# akabeacon_circle_MDBT40_type1.net
KiCad netlist of a schematic drawn in EAGLE
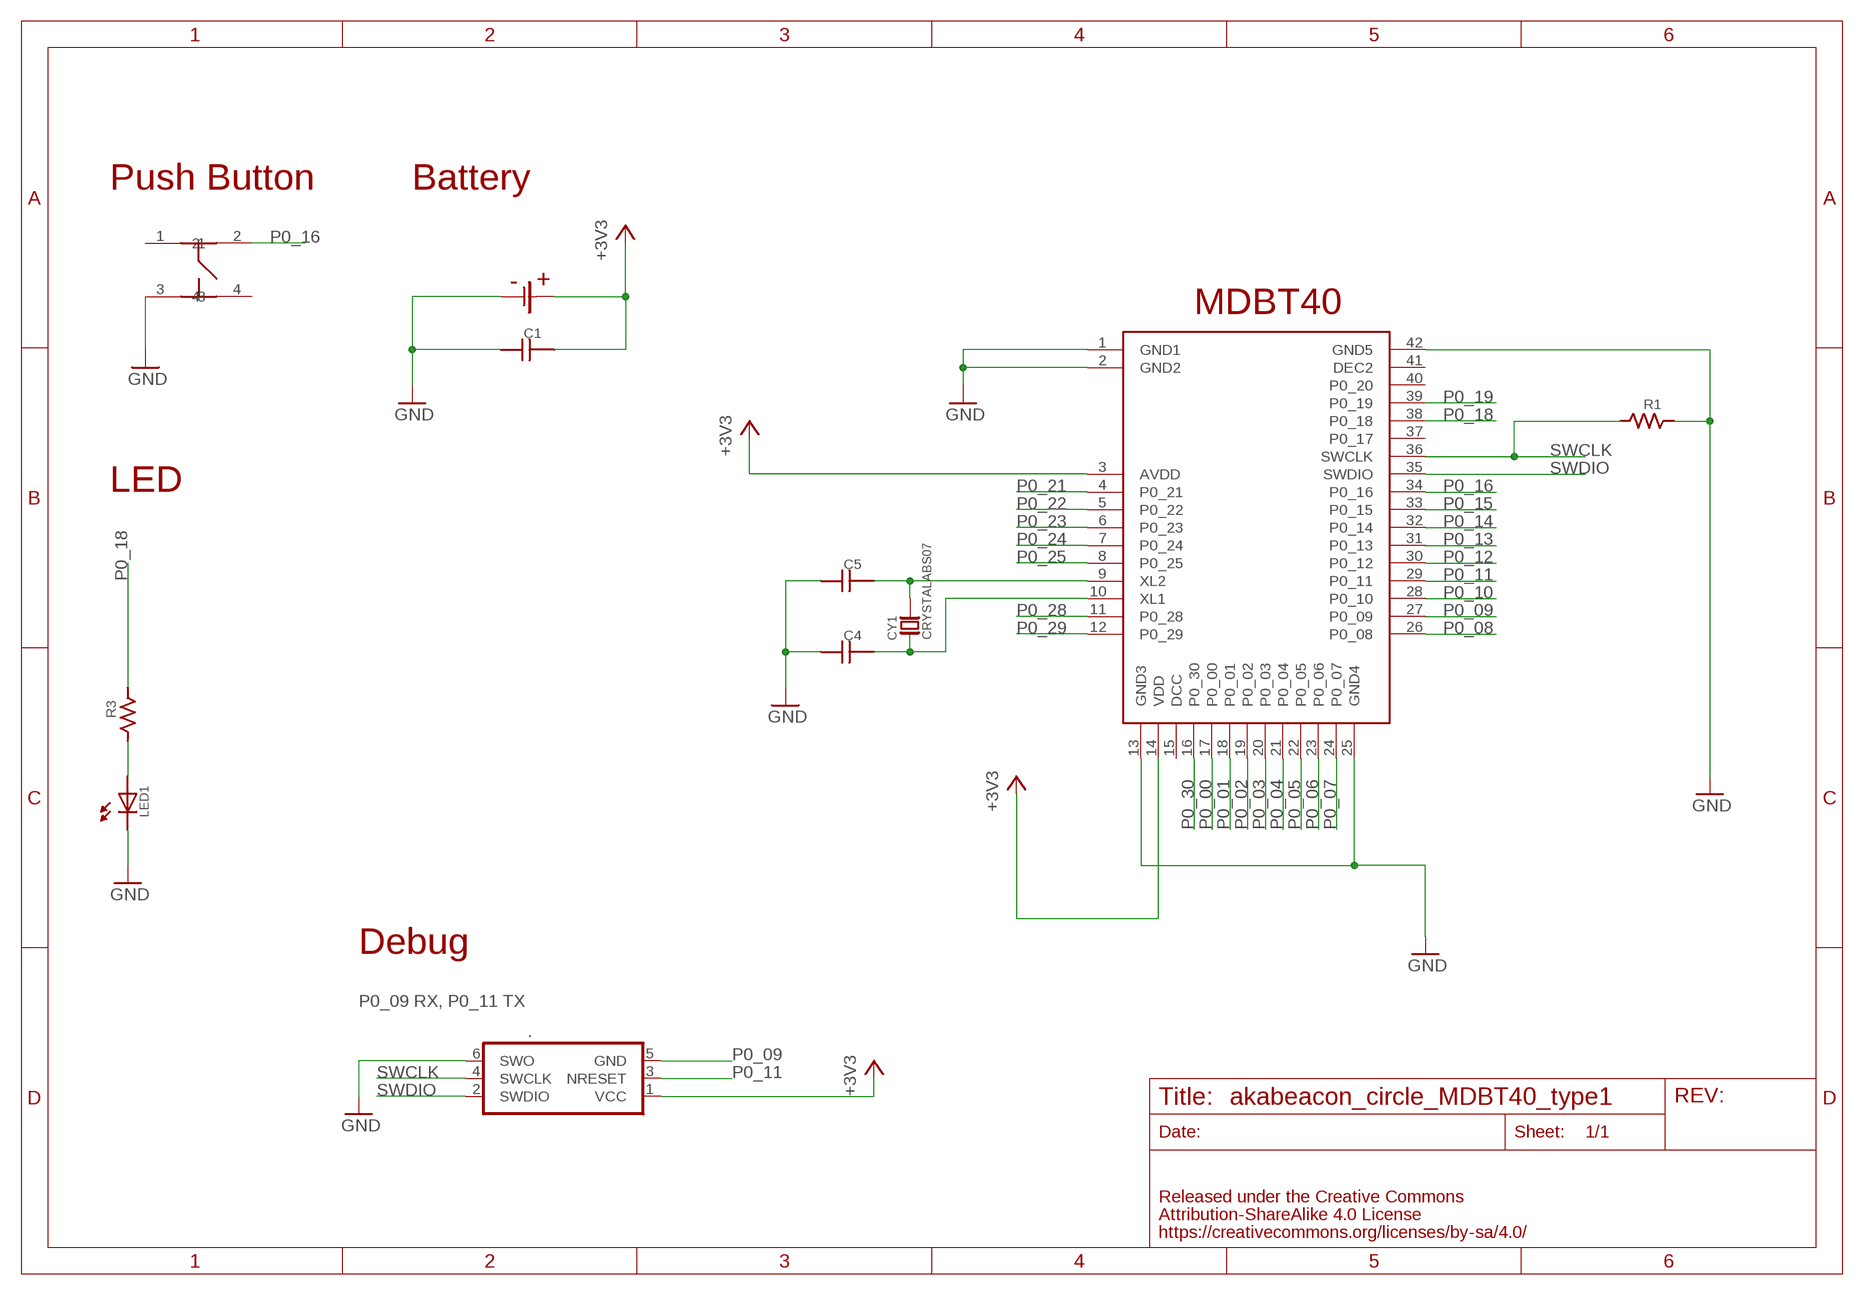
[diagram p0: schematic, sheet 1]

(export (version "E")
  (design (tool "Eeschema 10.0.6"))
  (components
    (comp (ref ".")
      (value "TC2030-IDC-NL")
      (footprint "eagle-import:TC2030-IDC-NL")
      (libsource (lib "eagle-import") (part "TC2030-IDC-NL"))
    )
    (comp (ref "C1")
      (value "CAPACITOR-0603")
      (footprint "eagle-import:0603")
      (libsource (lib "eagle-import") (part "CAPACITOR-0603"))
    )
    (comp (ref "C4")
      (value "CAPACITOR-0603")
      (footprint "eagle-import:0603")
      (libsource (lib "eagle-import") (part "CAPACITOR-0603"))
    )
    (comp (ref "C5")
      (value "CAPACITOR-0603")
      (footprint "eagle-import:0603")
      (libsource (lib "eagle-import") (part "CAPACITOR-0603"))
    )
    (comp (ref "CY1")
      (value "CRYSTALABS07")
      (footprint "eagle-import:ABRACOM-ABS07-32.768KHZ")
      (libsource (lib "eagle-import") (part "CRYSTALABS07"))
    )
    (comp (ref "LED1")
      (value "LED-0603")
      (footprint "eagle-import:0603")
      (libsource (lib "eagle-import") (part "LED-0603"))
    )
    (comp (ref "R1")
      (value "RESISTOR-0603")
      (footprint "eagle-import:0603")
      (libsource (lib "eagle-import") (part "RESISTOR-0603"))
    )
    (comp (ref "R3")
      (value "RESISTOR-0603")
      (footprint "eagle-import:0603")
      (libsource (lib "eagle-import") (part "RESISTOR-0603"))
    )
    (comp (ref "U$1")
      (value "RAYTAC-MDBT40")
      (footprint "eagle-import:RAYTAC-MDBT40")
      (libsource (lib "eagle-import") (part "RAYTAC-MDBT40"))
    )
    (comp (ref "U$2")
      (value "CH031-2477LF")
      (footprint "eagle-import:CH031-2477LF")
      (libsource (lib "eagle-import") (part "CH031-2477LF"))
    )
    (comp (ref "U$5")
      (value "SWICTH-4P(KMR2)")
      (footprint "eagle-import:SWITCH-4P(KMR2)")
      (libsource (lib "eagle-import") (part "SWICTH-4P(KMR2)"))
    )
  )
  (nets
    (net (code "1") (name "+3V3") (class "Default")
      (node (ref ".") (pin "1") (pinfunction "VCC_1") (pintype "passive"))
      (node (ref "C1") (pin "2") (pinfunction "2_2") (pintype "passive"))
      (node (ref "U$1") (pin "14") (pinfunction "VDD_14") (pintype "bidirectional"))
      (node (ref "U$1") (pin "3") (pinfunction "AVDD_3") (pintype "bidirectional"))
      (node (ref "U$2") (pin "+") (pinfunction "+_+") (pintype "bidirectional"))
    )
    (net (code "2") (name "/P0_00") (class "Default")
      (node (ref "U$1") (pin "17") (pinfunction "P0_00_17") (pintype "bidirectional"))
    )
    (net (code "3") (name "/P0_01") (class "Default")
      (node (ref "U$1") (pin "18") (pinfunction "P0_01_18") (pintype "bidirectional"))
    )
    (net (code "4") (name "/P0_02") (class "Default")
      (node (ref "U$1") (pin "19") (pinfunction "P0_02_19") (pintype "bidirectional"))
    )
    (net (code "5") (name "/P0_03") (class "Default")
      (node (ref "U$1") (pin "20") (pinfunction "P0_03_20") (pintype "bidirectional"))
    )
    (net (code "6") (name "/P0_04") (class "Default")
      (node (ref "U$1") (pin "21") (pinfunction "P0_04_21") (pintype "bidirectional"))
    )
    (net (code "7") (name "/P0_05") (class "Default")
      (node (ref "U$1") (pin "22") (pinfunction "P0_05_22") (pintype "bidirectional"))
    )
    (net (code "8") (name "/P0_06") (class "Default")
      (node (ref "U$1") (pin "23") (pinfunction "P0_06_23") (pintype "bidirectional"))
    )
    (net (code "9") (name "/P0_07") (class "Default")
      (node (ref "U$1") (pin "24") (pinfunction "P0_07_24") (pintype "bidirectional"))
    )
    (net (code "10") (name "/P0_08") (class "Default")
      (node (ref "U$1") (pin "26") (pinfunction "P0_08_26") (pintype "bidirectional"))
    )
    (net (code "11") (name "/P0_09") (class "Default")
      (node (ref ".") (pin "5") (pinfunction "GND_5") (pintype "passive"))
      (node (ref "U$1") (pin "27") (pinfunction "P0_09_27") (pintype "bidirectional"))
    )
    (net (code "12") (name "/P0_10") (class "Default")
      (node (ref "U$1") (pin "28") (pinfunction "P0_10_28") (pintype "bidirectional"))
    )
    (net (code "13") (name "/P0_11") (class "Default")
      (node (ref ".") (pin "3") (pinfunction "NRESET_3") (pintype "passive"))
      (node (ref "U$1") (pin "29") (pinfunction "P0_11_29") (pintype "bidirectional"))
    )
    (net (code "14") (name "/P0_12") (class "Default")
      (node (ref "U$1") (pin "30") (pinfunction "P0_12_30") (pintype "bidirectional"))
    )
    (net (code "15") (name "/P0_13") (class "Default")
      (node (ref "U$1") (pin "31") (pinfunction "P0_13_31") (pintype "bidirectional"))
    )
    (net (code "16") (name "/P0_14") (class "Default")
      (node (ref "U$1") (pin "32") (pinfunction "P0_14_32") (pintype "bidirectional"))
    )
    (net (code "17") (name "/P0_15") (class "Default")
      (node (ref "U$1") (pin "33") (pinfunction "P0_15_33") (pintype "bidirectional"))
    )
    (net (code "18") (name "/P0_16") (class "Default")
      (node (ref "U$1") (pin "34") (pinfunction "P0_16_34") (pintype "bidirectional"))
      (node (ref "U$5") (pin "2") (pinfunction "2_2") (pintype "bidirectional"))
    )
    (net (code "19") (name "/P0_18") (class "Default")
      (node (ref "R3") (pin "2") (pinfunction "2_2") (pintype "bidirectional"))
      (node (ref "U$1") (pin "38") (pinfunction "P0_18_38") (pintype "bidirectional"))
    )
    (net (code "20") (name "/P0_19") (class "Default")
      (node (ref "U$1") (pin "39") (pinfunction "P0_19_39") (pintype "bidirectional"))
    )
    (net (code "21") (name "/P0_21") (class "Default")
      (node (ref "U$1") (pin "4") (pinfunction "P0_21_4") (pintype "bidirectional"))
    )
    (net (code "22") (name "/P0_22") (class "Default")
      (node (ref "U$1") (pin "5") (pinfunction "P0_22_5") (pintype "bidirectional"))
    )
    (net (code "23") (name "/P0_23") (class "Default")
      (node (ref "U$1") (pin "6") (pinfunction "P0_23_6") (pintype "bidirectional"))
    )
    (net (code "24") (name "/P0_24") (class "Default")
      (node (ref "U$1") (pin "7") (pinfunction "P0_24_7") (pintype "bidirectional"))
    )
    (net (code "25") (name "/P0_25") (class "Default")
      (node (ref "U$1") (pin "8") (pinfunction "P0_25_8") (pintype "bidirectional"))
    )
    (net (code "26") (name "/P0_28") (class "Default")
      (node (ref "U$1") (pin "11") (pinfunction "P0_28_11") (pintype "bidirectional"))
    )
    (net (code "27") (name "/P0_29") (class "Default")
      (node (ref "U$1") (pin "12") (pinfunction "P0_29_12") (pintype "bidirectional"))
    )
    (net (code "28") (name "/P0_30") (class "Default")
      (node (ref "U$1") (pin "16") (pinfunction "P0_30_16") (pintype "bidirectional"))
    )
    (net (code "29") (name "/SWCLK") (class "Default")
      (node (ref ".") (pin "4") (pinfunction "SWCLK_4") (pintype "passive"))
      (node (ref "R1") (pin "1") (pinfunction "1_1") (pintype "bidirectional"))
      (node (ref "U$1") (pin "36") (pinfunction "SWCLK_36") (pintype "bidirectional"))
    )
    (net (code "30") (name "/SWDIO") (class "Default")
      (node (ref ".") (pin "2") (pinfunction "SWDIO_2") (pintype "passive"))
      (node (ref "U$1") (pin "35") (pinfunction "SWDIO_35") (pintype "bidirectional"))
    )
    (net (code "31") (name "GND") (class "Default")
      (node (ref ".") (pin "6") (pinfunction "SWO_6") (pintype "passive"))
      (node (ref "C1") (pin "1") (pinfunction "1_1") (pintype "passive"))
      (node (ref "C4") (pin "1") (pinfunction "1_1") (pintype "passive"))
      (node (ref "C5") (pin "1") (pinfunction "1_1") (pintype "passive"))
      (node (ref "LED1") (pin "CATHODE") (pinfunction "CATHODE_CATHODE") (pintype "passive"))
      (node (ref "R1") (pin "2") (pinfunction "2_2") (pintype "bidirectional"))
      (node (ref "U$1") (pin "1") (pinfunction "GND1_1") (pintype "bidirectional"))
      (node (ref "U$1") (pin "13") (pinfunction "GND3_13") (pintype "bidirectional"))
      (node (ref "U$1") (pin "2") (pinfunction "GND2_2") (pintype "bidirectional"))
      (node (ref "U$1") (pin "25") (pinfunction "GND4_25") (pintype "bidirectional"))
      (node (ref "U$1") (pin "42") (pinfunction "GND5_42") (pintype "bidirectional"))
      (node (ref "U$2") (pin "-") (pinfunction "-_-") (pintype "bidirectional"))
      (node (ref "U$5") (pin "3") (pinfunction "3_3") (pintype "bidirectional"))
    )
    (net (code "32") (name "Net-(LED1-PadANODE)") (class "Default")
      (node (ref "LED1") (pin "ANODE") (pinfunction "ANODE_ANODE") (pintype "passive"))
      (node (ref "R3") (pin "1") (pinfunction "1_1") (pintype "bidirectional"))
    )
    (net (code "33") (name "Net-(U$1-XL1)") (class "Default")
      (node (ref "C4") (pin "2") (pinfunction "2_2") (pintype "passive"))
      (node (ref "CY1") (pin "P$1") (pinfunction "P$1_P$1") (pintype "bidirectional"))
      (node (ref "U$1") (pin "10") (pinfunction "XL1_10") (pintype "bidirectional"))
    )
    (net (code "34") (name "Net-(U$1-XL2)") (class "Default")
      (node (ref "C5") (pin "2") (pinfunction "2_2") (pintype "passive"))
      (node (ref "CY1") (pin "P$2") (pinfunction "P$2_P$2") (pintype "bidirectional"))
      (node (ref "U$1") (pin "9") (pinfunction "XL2_9") (pintype "bidirectional"))
    )
    (net (code "35") (name "unconnected-(U$1-DCC-Pad15)") (class "Default")
      (node (ref "U$1") (pin "15") (pinfunction "DCC_15") (pintype "bidirectional"))
    )
    (net (code "36") (name "unconnected-(U$1-DEC2-Pad41)") (class "Default")
      (node (ref "U$1") (pin "41") (pinfunction "DEC2_41") (pintype "bidirectional"))
    )
    (net (code "37") (name "unconnected-(U$1-P0_17-Pad37)") (class "Default")
      (node (ref "U$1") (pin "37") (pinfunction "P0_17_37") (pintype "bidirectional"))
    )
    (net (code "38") (name "unconnected-(U$1-P0_20-Pad40)") (class "Default")
      (node (ref "U$1") (pin "40") (pinfunction "P0_20_40") (pintype "bidirectional"))
    )
    (net (code "39") (name "unconnected-(U$5-Pad1)") (class "Default")
      (node (ref "U$5") (pin "1") (pinfunction "1_1") (pintype "bidirectional"))
    )
    (net (code "40") (name "unconnected-(U$5-Pad4)") (class "Default")
      (node (ref "U$5") (pin "4") (pinfunction "4_4") (pintype "bidirectional"))
    )
  )
)
